# EthernetMotorController.net
KiCad netlist of a schematic drawn in Altium Designer
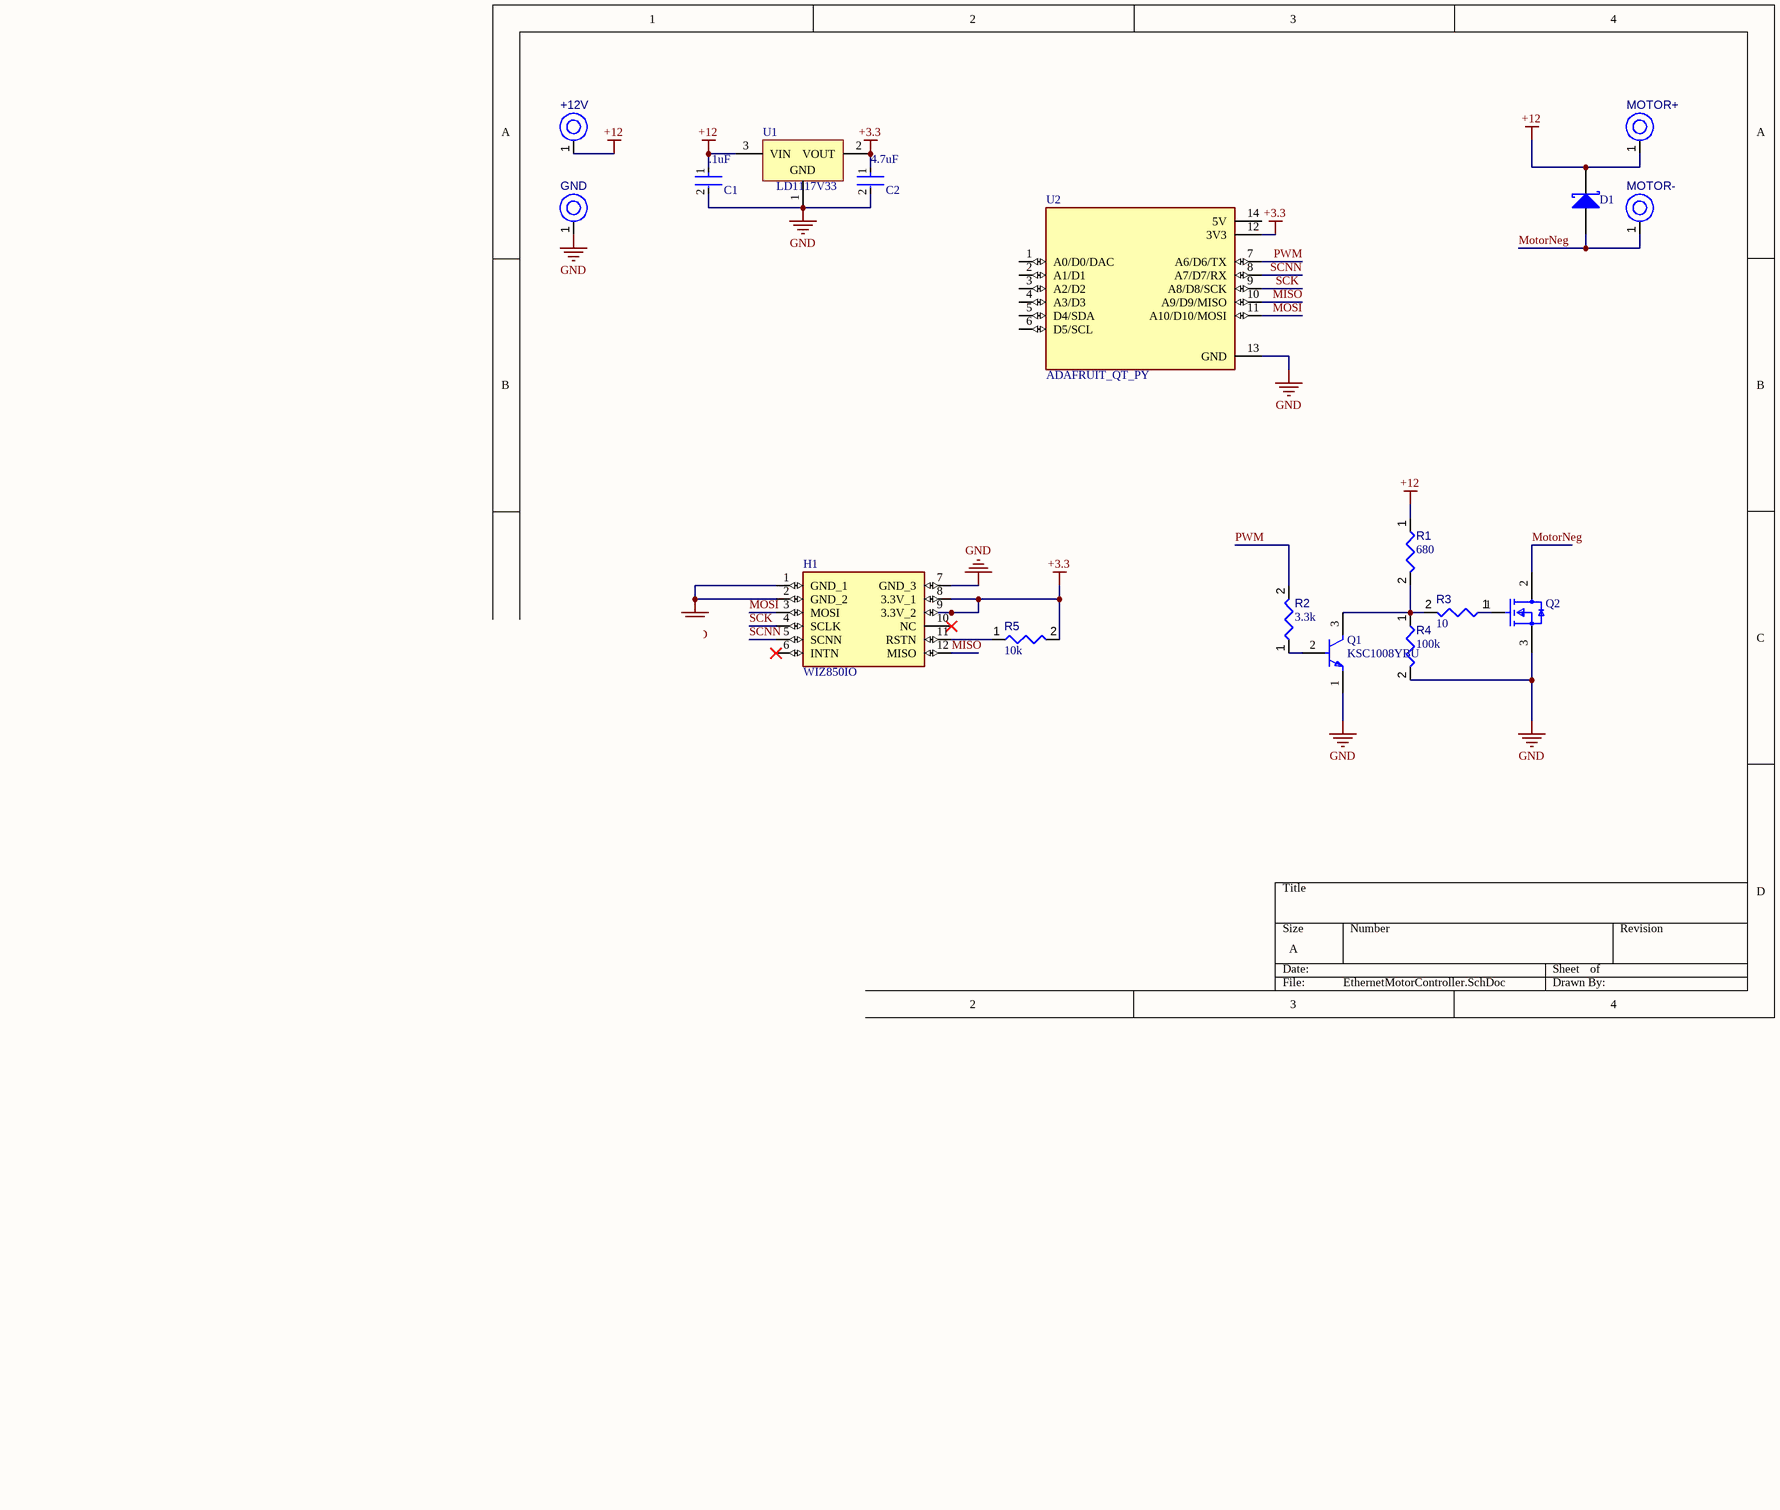
[diagram p0: EthernetMotorController.SchDoc]

(export (version "E")
  (design (tool "Eeschema 10.0.6"))
  (components
    (comp (ref "+12V")
      (value "PTH-M2D5X5")
      (footprint "PTH-M2D5X5")
      (description "M2 PTH (2.5mm), 5mm pad")
      (libsource (lib "Lyle Antieau") (part "CMP-00028-00000-1"))
    )
    (comp (ref "C1")
      (value ".1uF")
      (footprint "FP-RDEWK1-MFG")
      (description "Cap Ceramic 4.7uF 100V X7S 20% Radial 5mm 125C Bulk")
      (libsource (lib "Lyle Antieau") (part "02cd4be3c70576c341d710602a673aa"))
    )
    (comp (ref "C2")
      (value "4.7uF")
      (footprint "FP-RDEWK1-MFG")
      (description "Cap Ceramic 4.7uF 100V X7S 20% Radial 5mm 125C Bulk")
      (libsource (lib "Lyle Antieau") (part "02cd4be3c70576c341d710602a673aa"))
    )
    (comp (ref "D1")
      (value "MBR360G")
      (footprint "ONSC-AXIAL_LEAD-2-267-05_V")
      (description "Axial Lead Rectifier, 60 V, 3 A, -65 to 150 degC, 2-Pin DO-201AD, RoHS, Bag")
      (libsource (lib "Altium Content Vault") (part "DSKY-AK-2"))
    )
    (comp (ref "GND")
      (value "PTH-M2D5X5")
      (footprint "PTH-M2D5X5")
      (description "M2 PTH (2.5mm), 5mm pad")
      (libsource (lib "Lyle Antieau") (part "CMP-00028-00000-1"))
    )
    (comp (ref "H1")
      (value "WIZ850IO")
      (footprint "WIZ850IO")
      (description "Ethernet - 10/100 Base-T/TX PHY SPI Interface Module")
      (fields (field (name "MF") "WIZnet"))
      (libsource (lib "Lyle Antieau") (part "WIZ850IO"))
    )
    (comp (ref "MOTOR+")
      (value "PTH-M2D5X5")
      (footprint "PTH-M2D5X5")
      (description "M2 PTH (2.5mm), 5mm pad")
      (libsource (lib "Lyle Antieau") (part "CMP-00028-00000-1"))
    )
    (comp (ref "MOTOR-")
      (value "PTH-M2D5X5")
      (footprint "PTH-M2D5X5")
      (description "M2 PTH (2.5mm), 5mm pad")
      (libsource (lib "Lyle Antieau") (part "CMP-00028-00000-1"))
    )
    (comp (ref "Q1")
      (value "KSC1008YBU")
      (footprint "FP-135AN-MFG")
      (libsource (lib "Altium Content Vault") (part "a64cbfbad643015290886283bc510aa"))
    )
    (comp (ref "Q2")
      (value "CSD18534KCS")
      (footprint "FP-KCS0003B-MFG")
      (description "60-V, N channel NexFET™ power MOSFET, single TO-220, 9.5 mOhm 3-TO-220 -55 to 175")
      (libsource (lib "Lyle Antieau") (part "6a2845f377bf806f212caa2313e0e79"))
    )
    (comp (ref "R1")
      (value "680")
      (footprint "RESA60-630X240")
      (description "Axial Resistor, 100 Ohm, +/- 1%, 0.25 W, -55 to 155 degC, 2-Pin THD, RoHS, Bulk")
      (fields (field (name "MANUFACTURER") "Yageo") (field (name "TOLERANCE") "1%"))
      (libsource (lib "Lyle Antieau") (part "RES-2"))
    )
    (comp (ref "R2")
      (value "3.3k")
      (footprint "RESA60-630X240")
      (description "Axial Resistor, 10 KOhm, +/- 1%, 0.25 W, -55 to 155 degC, 2-Pin THD, RoHS, Bulk")
      (fields (field (name "TOLERANCE") "1%") (field (name "POWER") "250mW"))
      (libsource (lib "Lyle Antieau") (part "RES-2"))
    )
    (comp (ref "R3")
      (value "10")
      (footprint "RESA60-630X240")
      (description "Axial Resistor, 100 Ohm, +/- 1%, 0.25 W, -55 to 155 degC, 2-Pin THD, RoHS, Bulk")
      (fields (field (name "MANUFACTURER") "Yageo") (field (name "TOLERANCE") "1%"))
      (libsource (lib "Lyle Antieau") (part "RES-2"))
    )
    (comp (ref "R4")
      (value "100k")
      (footprint "RESA60-630X240")
      (description "Axial Resistor, 100 Ohm, +/- 1%, 0.25 W, -55 to 155 degC, 2-Pin THD, RoHS, Bulk")
      (fields (field (name "MANUFACTURER") "Yageo") (field (name "TOLERANCE") "1%"))
      (libsource (lib "Lyle Antieau") (part "RES-2"))
    )
    (comp (ref "R5")
      (value "10k")
      (footprint "RESA60-630X240")
      (description "Axial Resistor, 100 Ohm, +/- 1%, 0.25 W, -55 to 155 degC, 2-Pin THD, RoHS, Bulk")
      (fields (field (name "MANUFACTURER") "Yageo") (field (name "TOLERANCE") "1%"))
      (libsource (lib "Lyle Antieau") (part "RES-2"))
    )
    (comp (ref "U1")
      (value "LD1117V33")
      (footprint "STM-TO220-3")
      (fields (field (name "MANUFACTURER") "STMicroelectronics") (field (name "POWER") "12W"))
      (libsource (lib "Lyle Antieau") (part "STM-LD1117-V33"))
    )
    (comp (ref "U2")
      (value "ADAFRUIT_QT_PY")
      (footprint "MODULE_ADAFRUIT_QT_PY")
      (description "Castellated Pads - SAMD21 Dev Board with STEMMA QT")
      (fields (field (name "MP") "Adafruit QT Py") (field (name "MF") "Adafruit Industries"))
      (libsource (lib "Lyle Antieau") (part "ADAFRUIT_QT_PY"))
    )
  )
  (nets
    (net (code "1") (name "+3.3") (class "Default")
      (node (ref "C2") (pin "1") (pinfunction "1_1") (pintype "passive"))
      (node (ref "H1") (pin "8") (pinfunction "3.3V_1_8") (pintype "bidirectional"))
      (node (ref "H1") (pin "9") (pinfunction "3.3V_2_9") (pintype "bidirectional"))
      (node (ref "R5") (pin "2") (pinfunction "2_2") (pintype "passive"))
      (node (ref "U1") (pin "2") (pinfunction "VOUT_2") (pintype "power_in"))
      (node (ref "U2") (pin "12") (pinfunction "3V3_12") (pintype "power_in"))
    )
    (net (code "2") (name "+12") (class "Default")
      (node (ref "+12V") (pin "1") (pinfunction "H1_1") (pintype "passive"))
      (node (ref "C1") (pin "1") (pinfunction "1_1") (pintype "passive"))
      (node (ref "D1") (pin "2") (pinfunction "K_2") (pintype "passive"))
      (node (ref "MOTOR+") (pin "1") (pinfunction "H1_1") (pintype "passive"))
      (node (ref "R1") (pin "1") (pinfunction "1_1") (pintype "passive"))
      (node (ref "U1") (pin "3") (pinfunction "VIN_3") (pintype "power_in"))
    )
    (net (code "3") (name "/MISO") (class "Default")
      (node (ref "H1") (pin "12") (pinfunction "MISO_12") (pintype "bidirectional"))
      (node (ref "U2") (pin "10") (pinfunction "A9/D9/MISO_10") (pintype "bidirectional"))
    )
    (net (code "4") (name "/MOSI") (class "Default")
      (node (ref "H1") (pin "3") (pinfunction "MOSI_3") (pintype "bidirectional"))
      (node (ref "U2") (pin "11") (pinfunction "A10/D10/MOSI_11") (pintype "bidirectional"))
    )
    (net (code "5") (name "/MotorNeg") (class "Default")
      (node (ref "D1") (pin "1") (pinfunction "A_1") (pintype "passive"))
      (node (ref "MOTOR-") (pin "1") (pinfunction "H1_1") (pintype "passive"))
      (node (ref "Q2") (pin "2") (pinfunction "Drain_2") (pintype "passive"))
    )
    (net (code "6") (name "/PWM") (class "Default")
      (node (ref "R2") (pin "2") (pinfunction "2_2") (pintype "passive"))
      (node (ref "U2") (pin "7") (pinfunction "A6/D6/TX_7") (pintype "bidirectional"))
    )
    (net (code "7") (name "/SCK") (class "Default")
      (node (ref "H1") (pin "4") (pinfunction "SCLK_4") (pintype "bidirectional"))
      (node (ref "U2") (pin "9") (pinfunction "A8/D8/SCK_9") (pintype "bidirectional"))
    )
    (net (code "8") (name "/SCNN") (class "Default")
      (node (ref "H1") (pin "5") (pinfunction "SCNN_5") (pintype "bidirectional"))
      (node (ref "U2") (pin "8") (pinfunction "A7/D7/RX_8") (pintype "bidirectional"))
    )
    (net (code "9") (name "GND") (class "Default")
      (node (ref "C1") (pin "2") (pinfunction "2_2") (pintype "passive"))
      (node (ref "C2") (pin "2") (pinfunction "2_2") (pintype "passive"))
      (node (ref "GND") (pin "1") (pinfunction "H1_1") (pintype "passive"))
      (node (ref "H1") (pin "1") (pinfunction "GND_1_1") (pintype "bidirectional"))
      (node (ref "H1") (pin "2") (pinfunction "GND_2_2") (pintype "bidirectional"))
      (node (ref "H1") (pin "7") (pinfunction "GND_3_7") (pintype "bidirectional"))
      (node (ref "Q1") (pin "1") (pinfunction "E_1") (pintype "passive"))
      (node (ref "Q2") (pin "3") (pinfunction "Source_3") (pintype "passive"))
      (node (ref "R4") (pin "2") (pinfunction "2_2") (pintype "passive"))
      (node (ref "U1") (pin "1") (pinfunction "GND_1") (pintype "power_in"))
      (node (ref "U2") (pin "13") (pinfunction "GND_13") (pintype "power_in"))
    )
    (net (code "10") (name "Net-(H1-RSTN)") (class "Default")
      (node (ref "H1") (pin "11") (pinfunction "RSTN_11") (pintype "bidirectional"))
      (node (ref "R5") (pin "1") (pinfunction "1_1") (pintype "passive"))
    )
    (net (code "11") (name "Net-(Q1-B)") (class "Default")
      (node (ref "Q1") (pin "2") (pinfunction "B_2") (pintype "passive"))
      (node (ref "R2") (pin "1") (pinfunction "1_1") (pintype "passive"))
    )
    (net (code "12") (name "Net-(Q1-C)") (class "Default")
      (node (ref "Q1") (pin "3") (pinfunction "C_3") (pintype "passive"))
      (node (ref "R1") (pin "2") (pinfunction "2_2") (pintype "passive"))
      (node (ref "R3") (pin "2") (pinfunction "2_2") (pintype "passive"))
      (node (ref "R4") (pin "1") (pinfunction "1_1") (pintype "passive"))
    )
    (net (code "13") (name "Net-(Q2-Gate)") (class "Default")
      (node (ref "Q2") (pin "1") (pinfunction "Gate_1") (pintype "passive"))
      (node (ref "R3") (pin "1") (pinfunction "1_1") (pintype "passive"))
    )
    (net (code "14") (name "unconnected-(H1-INTN-Pad6)") (class "Default")
      (node (ref "H1") (pin "6") (pinfunction "INTN_6") (pintype "bidirectional+no_connect"))
    )
    (net (code "15") (name "unconnected-(H1-NC-Pad10)") (class "Default")
      (node (ref "H1") (pin "10") (pinfunction "NC_10") (pintype "passive+no_connect"))
    )
    (net (code "16") (name "unconnected-(U2-5V-Pad14)") (class "Default")
      (node (ref "U2") (pin "14") (pinfunction "5V_14") (pintype "power_in"))
    )
    (net (code "17") (name "unconnected-(U2-A0{slash}D0{slash}DAC-Pad1)") (class "Default")
      (node (ref "U2") (pin "1") (pinfunction "A0/D0/DAC_1") (pintype "bidirectional"))
    )
    (net (code "18") (name "unconnected-(U2-A1{slash}D1-Pad2)") (class "Default")
      (node (ref "U2") (pin "2") (pinfunction "A1/D1_2") (pintype "bidirectional"))
    )
    (net (code "19") (name "unconnected-(U2-A2{slash}D2-Pad3)") (class "Default")
      (node (ref "U2") (pin "3") (pinfunction "A2/D2_3") (pintype "bidirectional"))
    )
    (net (code "20") (name "unconnected-(U2-A3{slash}D3-Pad4)") (class "Default")
      (node (ref "U2") (pin "4") (pinfunction "A3/D3_4") (pintype "bidirectional"))
    )
    (net (code "21") (name "unconnected-(U2-D4{slash}SDA-Pad5)") (class "Default")
      (node (ref "U2") (pin "5") (pinfunction "D4/SDA_5") (pintype "bidirectional"))
    )
    (net (code "22") (name "unconnected-(U2-D5{slash}SCL-Pad6)") (class "Default")
      (node (ref "U2") (pin "6") (pinfunction "D5/SCL_6") (pintype "bidirectional"))
    )
  )
)
